# shield.net
KiCad netlist of a schematic drawn in EAGLE
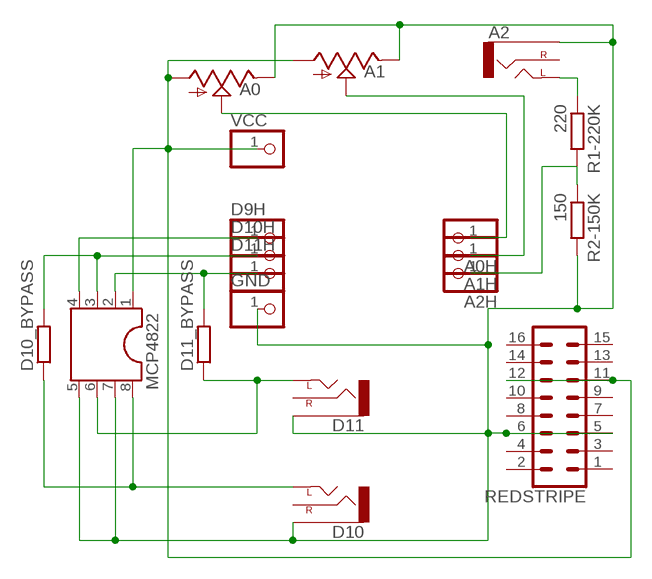
[diagram p0: schematic, sheet 1]

(export (version "E")
  (design (tool "Eeschema 10.0.6"))
  (components
    (comp (ref "A0")
      (value "9MM_SNAP-IN_POT_")
      (footprint "eagle-import:9MM_SNAP-IN_POT")
      (libsource (lib "eagle-import") (part "9MM_SNAP-IN_POT_"))
    )
    (comp (ref "A0H")
      (value "PINHD-1X1")
      (footprint "eagle-import:1X01")
      (libsource (lib "eagle-import") (part "PINHD-1X1"))
    )
    (comp (ref "A1")
      (value "9MM_SNAP-IN_POT_")
      (footprint "eagle-import:9MM_SNAP-IN_POT")
      (libsource (lib "eagle-import") (part "9MM_SNAP-IN_POT_"))
    )
    (comp (ref "A1H")
      (value "PINHD-1X1")
      (footprint "eagle-import:1X01")
      (libsource (lib "eagle-import") (part "PINHD-1X1"))
    )
    (comp (ref "A2")
      (value "THONKI-STEREO")
      (footprint "eagle-import:WQP-PJ366ST_JACK")
      (libsource (lib "eagle-import") (part "THONKI-STEREO"))
    )
    (comp (ref "A2H")
      (value "PINHD-1X1")
      (footprint "eagle-import:1X01")
      (libsource (lib "eagle-import") (part "PINHD-1X1"))
    )
    (comp (ref "D9H")
      (value "PINHD-1X1")
      (footprint "eagle-import:1X01")
      (libsource (lib "eagle-import") (part "PINHD-1X1"))
    )
    (comp (ref "D10")
      (value "THONKI-STEREO")
      (footprint "eagle-import:WQP-PJ366ST_JACK")
      (libsource (lib "eagle-import") (part "THONKI-STEREO"))
    )
    (comp (ref "D10H")
      (value "PINHD-1X1")
      (footprint "eagle-import:1X01")
      (libsource (lib "eagle-import") (part "PINHD-1X1"))
    )
    (comp (ref "D10_BYPASS")
      (value "RESISTOR10MM_RESISTOR")
      (footprint "eagle-import:10MM_RESISTOR")
      (libsource (lib "eagle-import") (part "RESISTOR10MM_RESISTOR"))
    )
    (comp (ref "D11")
      (value "THONKI-STEREO")
      (footprint "eagle-import:WQP-PJ366ST_JACK")
      (libsource (lib "eagle-import") (part "THONKI-STEREO"))
    )
    (comp (ref "D11H")
      (value "PINHD-1X1")
      (footprint "eagle-import:1X01")
      (libsource (lib "eagle-import") (part "PINHD-1X1"))
    )
    (comp (ref "D11_BYPASS")
      (value "RESISTOR10MM_RESISTOR")
      (footprint "eagle-import:10MM_RESISTOR")
      (libsource (lib "eagle-import") (part "RESISTOR10MM_RESISTOR"))
    )
    (comp (ref "GND")
      (value "PINHD-1X1")
      (footprint "eagle-import:1X01")
      (libsource (lib "eagle-import") (part "PINHD-1X1"))
    )
    (comp (ref "MCP4822")
      (value "DIL8")
      (footprint "eagle-import:DIL08")
      (libsource (lib "eagle-import") (part "DIL8"))
    )
    (comp (ref "R1-220K")
      (value "220")
      (footprint "eagle-import:7MM_RESISTOR")
      (libsource (lib "eagle-import") (part "RESISTOR7MM"))
    )
    (comp (ref "R2-150K")
      (value "150")
      (footprint "eagle-import:7MM_RESISTOR")
      (libsource (lib "eagle-import") (part "RESISTOR7MM"))
    )
    (comp (ref "REDSTRIPE")
      (value "CONN_08X2")
      (footprint "eagle-import:2X8")
      (libsource (lib "eagle-import") (part "CONN_08X2"))
    )
    (comp (ref "VCC")
      (value "PINHD-1X1")
      (footprint "eagle-import:1X01")
      (libsource (lib "eagle-import") (part "PINHD-1X1"))
    )
  )
  (nets
    (net (code "1") (name "Net-(A0-A)") (class "Default")
      (node (ref "A0") (pin "1") (pinfunction "A_1") (pintype "passive"))
      (node (ref "A1") (pin "1") (pinfunction "A_1") (pintype "passive"))
      (node (ref "MCP4822") (pin "1") (pinfunction "1_1") (pintype "passive"))
      (node (ref "REDSTRIPE") (pin "11") (pinfunction "11_11") (pintype "passive"))
      (node (ref "REDSTRIPE") (pin "12") (pinfunction "12_12") (pintype "passive"))
      (node (ref "VCC") (pin "1") (pinfunction "1_1") (pintype "passive"))
    )
    (net (code "2") (name "Net-(A0-E)") (class "Default")
      (node (ref "A0") (pin "3") (pinfunction "E_3") (pintype "passive"))
      (node (ref "A1") (pin "3") (pinfunction "E_3") (pintype "passive"))
      (node (ref "A2") (pin "P$3_SLEEVE") (pinfunction "SLEEVE_P$3_SLEEVE") (pintype "bidirectional"))
      (node (ref "D10") (pin "P$3_SLEEVE") (pinfunction "SLEEVE_P$3_SLEEVE") (pintype "bidirectional"))
      (node (ref "D11") (pin "P$3_SLEEVE") (pinfunction "SLEEVE_P$3_SLEEVE") (pintype "bidirectional"))
      (node (ref "GND") (pin "1") (pinfunction "1_1") (pintype "passive"))
      (node (ref "MCP4822") (pin "5") (pinfunction "5_5") (pintype "passive"))
      (node (ref "MCP4822") (pin "7") (pinfunction "7_7") (pintype "passive"))
      (node (ref "R2-150K") (pin "2") (pinfunction "2_2") (pintype "passive"))
      (node (ref "REDSTRIPE") (pin "5") (pinfunction "5_5") (pintype "passive"))
      (node (ref "REDSTRIPE") (pin "6") (pinfunction "6_6") (pintype "passive"))
    )
    (net (code "3") (name "Net-(A0-S)") (class "Default")
      (node (ref "A0") (pin "2") (pinfunction "S_2") (pintype "passive"))
      (node (ref "A0H") (pin "1") (pinfunction "1_1") (pintype "passive"))
    )
    (net (code "4") (name "Net-(A1-S)") (class "Default")
      (node (ref "A1") (pin "2") (pinfunction "S_2") (pintype "passive"))
      (node (ref "A1H") (pin "1") (pinfunction "1_1") (pintype "passive"))
    )
    (net (code "5") (name "Net-(A2-LEFT)") (class "Default")
      (node (ref "A2") (pin "P$1_TIP") (pinfunction "LEFT_P$1_TIP") (pintype "bidirectional"))
      (node (ref "R1-220K") (pin "1") (pinfunction "1_1") (pintype "passive"))
    )
    (net (code "6") (name "Net-(A2H-Pad1)") (class "Default")
      (node (ref "A2H") (pin "1") (pinfunction "1_1") (pintype "passive"))
      (node (ref "R1-220K") (pin "2") (pinfunction "2_2") (pintype "passive"))
      (node (ref "R2-150K") (pin "1") (pinfunction "1_1") (pintype "passive"))
    )
    (net (code "7") (name "Net-(D9H-Pad1)") (class "Default")
      (node (ref "D9H") (pin "1") (pinfunction "1_1") (pintype "passive"))
      (node (ref "MCP4822") (pin "4") (pinfunction "4_4") (pintype "passive"))
    )
    (net (code "8") (name "Net-(D10-LEFT)") (class "Default")
      (node (ref "D10") (pin "P$1_TIP") (pinfunction "LEFT_P$1_TIP") (pintype "bidirectional"))
      (node (ref "D10_BYPASS") (pin "1") (pinfunction "1_1") (pintype "passive"))
      (node (ref "MCP4822") (pin "8") (pinfunction "8_8") (pintype "passive"))
    )
    (net (code "9") (name "Net-(D10H-Pad1)") (class "Default")
      (node (ref "D10H") (pin "1") (pinfunction "1_1") (pintype "passive"))
      (node (ref "D10_BYPASS") (pin "2") (pinfunction "2_2") (pintype "passive"))
      (node (ref "MCP4822") (pin "3") (pinfunction "3_3") (pintype "passive"))
    )
    (net (code "10") (name "Net-(D11-LEFT)") (class "Default")
      (node (ref "D11") (pin "P$1_TIP") (pinfunction "LEFT_P$1_TIP") (pintype "bidirectional"))
      (node (ref "D11_BYPASS") (pin "1") (pinfunction "1_1") (pintype "passive"))
      (node (ref "MCP4822") (pin "6") (pinfunction "6_6") (pintype "passive"))
    )
    (net (code "11") (name "Net-(D11H-Pad1)") (class "Default")
      (node (ref "D11H") (pin "1") (pinfunction "1_1") (pintype "passive"))
      (node (ref "D11_BYPASS") (pin "2") (pinfunction "2_2") (pintype "passive"))
      (node (ref "MCP4822") (pin "2") (pinfunction "2_2") (pintype "passive"))
    )
    (net (code "12") (name "unconnected-(A2-RIGHT-PadP$2_SWITCH)") (class "Default")
      (node (ref "A2") (pin "P$2_SWITCH") (pinfunction "RIGHT_P$2_SWITCH") (pintype "bidirectional"))
    )
    (net (code "13") (name "unconnected-(D10-RIGHT-PadP$2_SWITCH)") (class "Default")
      (node (ref "D10") (pin "P$2_SWITCH") (pinfunction "RIGHT_P$2_SWITCH") (pintype "bidirectional"))
    )
    (net (code "14") (name "unconnected-(D11-RIGHT-PadP$2_SWITCH)") (class "Default")
      (node (ref "D11") (pin "P$2_SWITCH") (pinfunction "RIGHT_P$2_SWITCH") (pintype "bidirectional"))
    )
    (net (code "15") (name "unconnected-(REDSTRIPE-Pad1)") (class "Default")
      (node (ref "REDSTRIPE") (pin "1") (pinfunction "1_1") (pintype "passive"))
    )
    (net (code "16") (name "unconnected-(REDSTRIPE-Pad2)") (class "Default")
      (node (ref "REDSTRIPE") (pin "2") (pinfunction "2_2") (pintype "passive"))
    )
    (net (code "17") (name "unconnected-(REDSTRIPE-Pad3)") (class "Default")
      (node (ref "REDSTRIPE") (pin "3") (pinfunction "3_3") (pintype "passive"))
    )
    (net (code "18") (name "unconnected-(REDSTRIPE-Pad4)") (class "Default")
      (node (ref "REDSTRIPE") (pin "4") (pinfunction "4_4") (pintype "passive"))
    )
    (net (code "19") (name "unconnected-(REDSTRIPE-Pad7)") (class "Default")
      (node (ref "REDSTRIPE") (pin "7") (pinfunction "7_7") (pintype "passive"))
    )
    (net (code "20") (name "unconnected-(REDSTRIPE-Pad8)") (class "Default")
      (node (ref "REDSTRIPE") (pin "8") (pinfunction "8_8") (pintype "passive"))
    )
    (net (code "21") (name "unconnected-(REDSTRIPE-Pad9)") (class "Default")
      (node (ref "REDSTRIPE") (pin "9") (pinfunction "9_9") (pintype "passive"))
    )
    (net (code "22") (name "unconnected-(REDSTRIPE-Pad10)") (class "Default")
      (node (ref "REDSTRIPE") (pin "10") (pinfunction "10_10") (pintype "passive"))
    )
    (net (code "23") (name "unconnected-(REDSTRIPE-Pad13)") (class "Default")
      (node (ref "REDSTRIPE") (pin "13") (pinfunction "13_13") (pintype "passive"))
    )
    (net (code "24") (name "unconnected-(REDSTRIPE-Pad14)") (class "Default")
      (node (ref "REDSTRIPE") (pin "14") (pinfunction "14_14") (pintype "passive"))
    )
    (net (code "25") (name "unconnected-(REDSTRIPE-Pad15)") (class "Default")
      (node (ref "REDSTRIPE") (pin "15") (pinfunction "15_15") (pintype "passive"))
    )
    (net (code "26") (name "unconnected-(REDSTRIPE-Pad16)") (class "Default")
      (node (ref "REDSTRIPE") (pin "16") (pinfunction "16_16") (pintype "passive"))
    )
  )
)
